# Regulators.net
KiCad netlist of a schematic drawn in Altium Designer
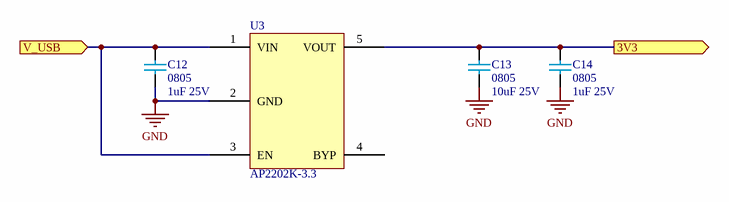
[diagram p0: Regulators.SchDoc]

(export (version "E")
  (design (tool "Eeschema 10.0.6"))
  (components
    (comp (ref "C12")
      (value "0805")
      (footprint "0805")
      (description "0805, X5R or better")
      (fields (field (name "ALTIUM_VALUE") "1uF 25V"))
      (libsource (lib "Chip_Passives") (part "Cap 1uF 25V"))
    )
    (comp (ref "C13")
      (value "0805")
      (footprint "0805")
      (description "0805, X5R or better")
      (fields (field (name "ALTIUM_VALUE") "10uF 25V"))
      (libsource (lib "Chip_Passives") (part "Cap 10uF 25V"))
    )
    (comp (ref "C14")
      (value "0805")
      (footprint "0805")
      (description "0805, X5R or better")
      (fields (field (name "ALTIUM_VALUE") "1uF 25V"))
      (libsource (lib "Chip_Passives") (part "Cap 1uF 25V"))
    )
    (comp (ref "U3")
      (value "AP2202K-3.3")
      (footprint "AP2202 - SOT95P270X145-5N")
      (description "3.3V 150mA LDO regulator")
      (libsource (lib "PowerSupply") (part "AP2202K-3.3"))
    )
  )
  (nets
    (net (code "1") (name "/3V3") (class "Default")
      (node (ref "C13") (pin "2") (pinfunction "2_2") (pintype "passive"))
      (node (ref "C14") (pin "2") (pinfunction "2_2") (pintype "passive"))
      (node (ref "U3") (pin "5") (pinfunction "VOUT_5") (pintype "passive"))
    )
    (net (code "2") (name "/V_USB") (class "Default")
      (node (ref "C12") (pin "2") (pinfunction "2_2") (pintype "passive"))
      (node (ref "U3") (pin "1") (pinfunction "VIN_1") (pintype "passive"))
      (node (ref "U3") (pin "3") (pinfunction "EN_3") (pintype "passive"))
    )
    (net (code "3") (name "GND") (class "Default")
      (node (ref "C12") (pin "1") (pinfunction "1_1") (pintype "passive"))
      (node (ref "C13") (pin "1") (pinfunction "1_1") (pintype "passive"))
      (node (ref "C14") (pin "1") (pinfunction "1_1") (pintype "passive"))
      (node (ref "U3") (pin "2") (pinfunction "GND_2") (pintype "passive"))
    )
    (net (code "4") (name "unconnected-(U3-BYP-Pad4)") (class "Default")
      (node (ref "U3") (pin "4") (pinfunction "BYP_4") (pintype "passive"))
    )
  )
)
